# NMT_UIO_INT.net
KiCad netlist of a schematic drawn in Altium Designer
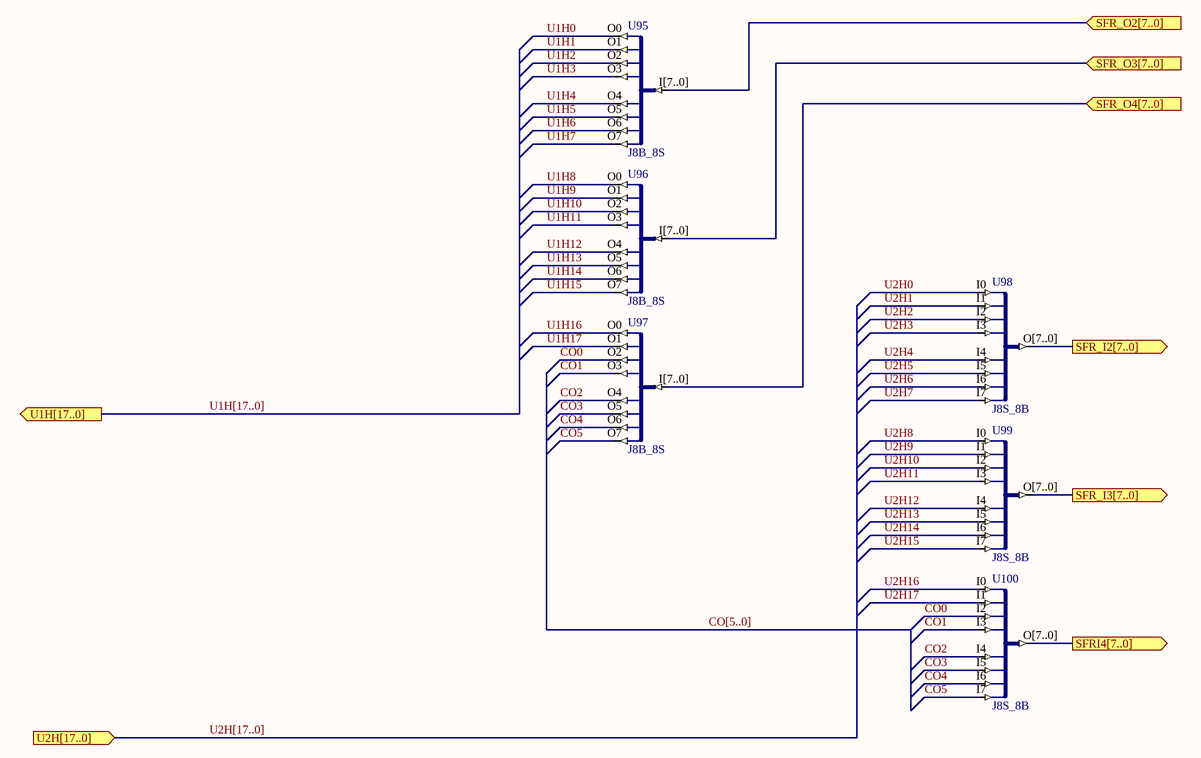
[diagram p0: NMT_UIO_INT.SCHDOC]

(export (version "E")
  (design (tool "Eeschema 10.0.6"))
  (components
    (comp (ref "U95")
      (value "J8B_8S")
      (description "8-Bit input bus to 8 single pin outputs")
      (fields (field (name "PUBLISHER") "Altium Limited"))
      (libsource (lib "FPGA Generic") (part "J8B_8S"))
    )
    (comp (ref "U96")
      (value "J8B_8S")
      (description "8-Bit input bus to 8 single pin outputs")
      (fields (field (name "PUBLISHER") "Altium Limited"))
      (libsource (lib "FPGA Generic") (part "J8B_8S"))
    )
    (comp (ref "U97")
      (value "J8B_8S")
      (description "8-Bit input bus to 8 single pin outputs")
      (fields (field (name "PUBLISHER") "Altium Limited"))
      (libsource (lib "FPGA Generic") (part "J8B_8S"))
    )
    (comp (ref "U98")
      (value "J8S_8B")
      (description "8 Single pin inputs to single 8-Bit output bus")
      (fields (field (name "PUBLISHER") "Altium Limited"))
      (libsource (lib "FPGA Generic") (part "J8S_8B"))
    )
    (comp (ref "U99")
      (value "J8S_8B")
      (description "8 Single pin inputs to single 8-Bit output bus")
      (fields (field (name "PUBLISHER") "Altium Limited"))
      (libsource (lib "FPGA Generic") (part "J8S_8B"))
    )
    (comp (ref "U100")
      (value "J8S_8B")
      (description "8 Single pin inputs to single 8-Bit output bus")
      (fields (field (name "PUBLISHER") "Altium Limited"))
      (libsource (lib "FPGA Generic") (part "J8S_8B"))
    )
  )
  (nets
    (net (code "49") (name "/CO0") (class "Default")
      (node (ref "U100") (pin "I2") (pinfunction "I2_I2") (pintype "input"))
      (node (ref "U97") (pin "O2") (pinfunction "O2_O2") (pintype "output"))
    )
    (net (code "50") (name "/CO1") (class "Default")
      (node (ref "U100") (pin "I3") (pinfunction "I3_I3") (pintype "input"))
      (node (ref "U97") (pin "O3") (pinfunction "O3_O3") (pintype "output"))
    )
    (net (code "51") (name "/CO2") (class "Default")
      (node (ref "U100") (pin "I4") (pinfunction "I4_I4") (pintype "input"))
      (node (ref "U97") (pin "O4") (pinfunction "O4_O4") (pintype "output"))
    )
    (net (code "52") (name "/CO3") (class "Default")
      (node (ref "U100") (pin "I5") (pinfunction "I5_I5") (pintype "input"))
      (node (ref "U97") (pin "O5") (pinfunction "O5_O5") (pintype "output"))
    )
    (net (code "53") (name "/CO4") (class "Default")
      (node (ref "U100") (pin "I6") (pinfunction "I6_I6") (pintype "input"))
      (node (ref "U97") (pin "O6") (pinfunction "O6_O6") (pintype "output"))
    )
    (net (code "54") (name "/CO5") (class "Default")
      (node (ref "U100") (pin "I7") (pinfunction "I7_I7") (pintype "input"))
      (node (ref "U97") (pin "O7") (pinfunction "O7_O7") (pintype "output"))
    )
    (net (code "56") (name "/SFRI4[7..0]") (class "Default")
      (node (ref "U100") (pin "O[7..0]") (pinfunction "O[7..0]_O[7..0]") (pintype "output"))
    )
    (net (code "57") (name "/SFR_I2[7..0]") (class "Default")
      (node (ref "U98") (pin "O[7..0]") (pinfunction "O[7..0]_O[7..0]") (pintype "output"))
    )
    (net (code "58") (name "/SFR_I3[7..0]") (class "Default")
      (node (ref "U99") (pin "O[7..0]") (pinfunction "O[7..0]_O[7..0]") (pintype "output"))
    )
    (net (code "59") (name "/SFR_O2[7..0]") (class "Default")
      (node (ref "U95") (pin "I[7..0]") (pinfunction "I[7..0]_I[7..0]") (pintype "input"))
    )
    (net (code "60") (name "/SFR_O3[7..0]") (class "Default")
      (node (ref "U96") (pin "I[7..0]") (pinfunction "I[7..0]_I[7..0]") (pintype "input"))
    )
    (net (code "61") (name "/SFR_O4[7..0]") (class "Default")
      (node (ref "U97") (pin "I[7..0]") (pinfunction "I[7..0]_I[7..0]") (pintype "input"))
    )
    (net (code "62") (name "/U1H0") (class "Default")
      (node (ref "U95") (pin "O0") (pinfunction "O0_O0") (pintype "output"))
    )
    (net (code "63") (name "/U1H1") (class "Default")
      (node (ref "U95") (pin "O1") (pinfunction "O1_O1") (pintype "output"))
    )
    (net (code "64") (name "/U1H2") (class "Default")
      (node (ref "U95") (pin "O2") (pinfunction "O2_O2") (pintype "output"))
    )
    (net (code "65") (name "/U1H3") (class "Default")
      (node (ref "U95") (pin "O3") (pinfunction "O3_O3") (pintype "output"))
    )
    (net (code "66") (name "/U1H4") (class "Default")
      (node (ref "U95") (pin "O4") (pinfunction "O4_O4") (pintype "output"))
    )
    (net (code "67") (name "/U1H5") (class "Default")
      (node (ref "U95") (pin "O5") (pinfunction "O5_O5") (pintype "output"))
    )
    (net (code "68") (name "/U1H6") (class "Default")
      (node (ref "U95") (pin "O6") (pinfunction "O6_O6") (pintype "output"))
    )
    (net (code "69") (name "/U1H7") (class "Default")
      (node (ref "U95") (pin "O7") (pinfunction "O7_O7") (pintype "output"))
    )
    (net (code "70") (name "/U1H8") (class "Default")
      (node (ref "U96") (pin "O0") (pinfunction "O0_O0") (pintype "output"))
    )
    (net (code "71") (name "/U1H9") (class "Default")
      (node (ref "U96") (pin "O1") (pinfunction "O1_O1") (pintype "output"))
    )
    (net (code "72") (name "/U1H10") (class "Default")
      (node (ref "U96") (pin "O2") (pinfunction "O2_O2") (pintype "output"))
    )
    (net (code "73") (name "/U1H11") (class "Default")
      (node (ref "U96") (pin "O3") (pinfunction "O3_O3") (pintype "output"))
    )
    (net (code "74") (name "/U1H12") (class "Default")
      (node (ref "U96") (pin "O4") (pinfunction "O4_O4") (pintype "output"))
    )
    (net (code "75") (name "/U1H13") (class "Default")
      (node (ref "U96") (pin "O5") (pinfunction "O5_O5") (pintype "output"))
    )
    (net (code "76") (name "/U1H14") (class "Default")
      (node (ref "U96") (pin "O6") (pinfunction "O6_O6") (pintype "output"))
    )
    (net (code "77") (name "/U1H15") (class "Default")
      (node (ref "U96") (pin "O7") (pinfunction "O7_O7") (pintype "output"))
    )
    (net (code "78") (name "/U1H16") (class "Default")
      (node (ref "U97") (pin "O0") (pinfunction "O0_O0") (pintype "output"))
    )
    (net (code "79") (name "/U1H17") (class "Default")
      (node (ref "U97") (pin "O1") (pinfunction "O1_O1") (pintype "output"))
    )
    (net (code "81") (name "/U2H0") (class "Default")
      (node (ref "U98") (pin "I0") (pinfunction "I0_I0") (pintype "input"))
    )
    (net (code "82") (name "/U2H1") (class "Default")
      (node (ref "U98") (pin "I1") (pinfunction "I1_I1") (pintype "input"))
    )
    (net (code "83") (name "/U2H2") (class "Default")
      (node (ref "U98") (pin "I2") (pinfunction "I2_I2") (pintype "input"))
    )
    (net (code "84") (name "/U2H3") (class "Default")
      (node (ref "U98") (pin "I3") (pinfunction "I3_I3") (pintype "input"))
    )
    (net (code "85") (name "/U2H4") (class "Default")
      (node (ref "U98") (pin "I4") (pinfunction "I4_I4") (pintype "input"))
    )
    (net (code "86") (name "/U2H5") (class "Default")
      (node (ref "U98") (pin "I5") (pinfunction "I5_I5") (pintype "input"))
    )
    (net (code "87") (name "/U2H6") (class "Default")
      (node (ref "U98") (pin "I6") (pinfunction "I6_I6") (pintype "input"))
    )
    (net (code "88") (name "/U2H7") (class "Default")
      (node (ref "U98") (pin "I7") (pinfunction "I7_I7") (pintype "input"))
    )
    (net (code "89") (name "/U2H8") (class "Default")
      (node (ref "U99") (pin "I0") (pinfunction "I0_I0") (pintype "input"))
    )
    (net (code "90") (name "/U2H9") (class "Default")
      (node (ref "U99") (pin "I1") (pinfunction "I1_I1") (pintype "input"))
    )
    (net (code "91") (name "/U2H10") (class "Default")
      (node (ref "U99") (pin "I2") (pinfunction "I2_I2") (pintype "input"))
    )
    (net (code "92") (name "/U2H11") (class "Default")
      (node (ref "U99") (pin "I3") (pinfunction "I3_I3") (pintype "input"))
    )
    (net (code "93") (name "/U2H12") (class "Default")
      (node (ref "U99") (pin "I4") (pinfunction "I4_I4") (pintype "input"))
    )
    (net (code "94") (name "/U2H13") (class "Default")
      (node (ref "U99") (pin "I5") (pinfunction "I5_I5") (pintype "input"))
    )
    (net (code "95") (name "/U2H14") (class "Default")
      (node (ref "U99") (pin "I6") (pinfunction "I6_I6") (pintype "input"))
    )
    (net (code "96") (name "/U2H15") (class "Default")
      (node (ref "U99") (pin "I7") (pinfunction "I7_I7") (pintype "input"))
    )
    (net (code "97") (name "/U2H16") (class "Default")
      (node (ref "U100") (pin "I0") (pinfunction "I0_I0") (pintype "input"))
    )
    (net (code "98") (name "/U2H17") (class "Default")
      (node (ref "U100") (pin "I1") (pinfunction "I1_I1") (pintype "input"))
    )
  )
)
